# camera-ir-led.net
KiCad netlist of a schematic drawn in EAGLE
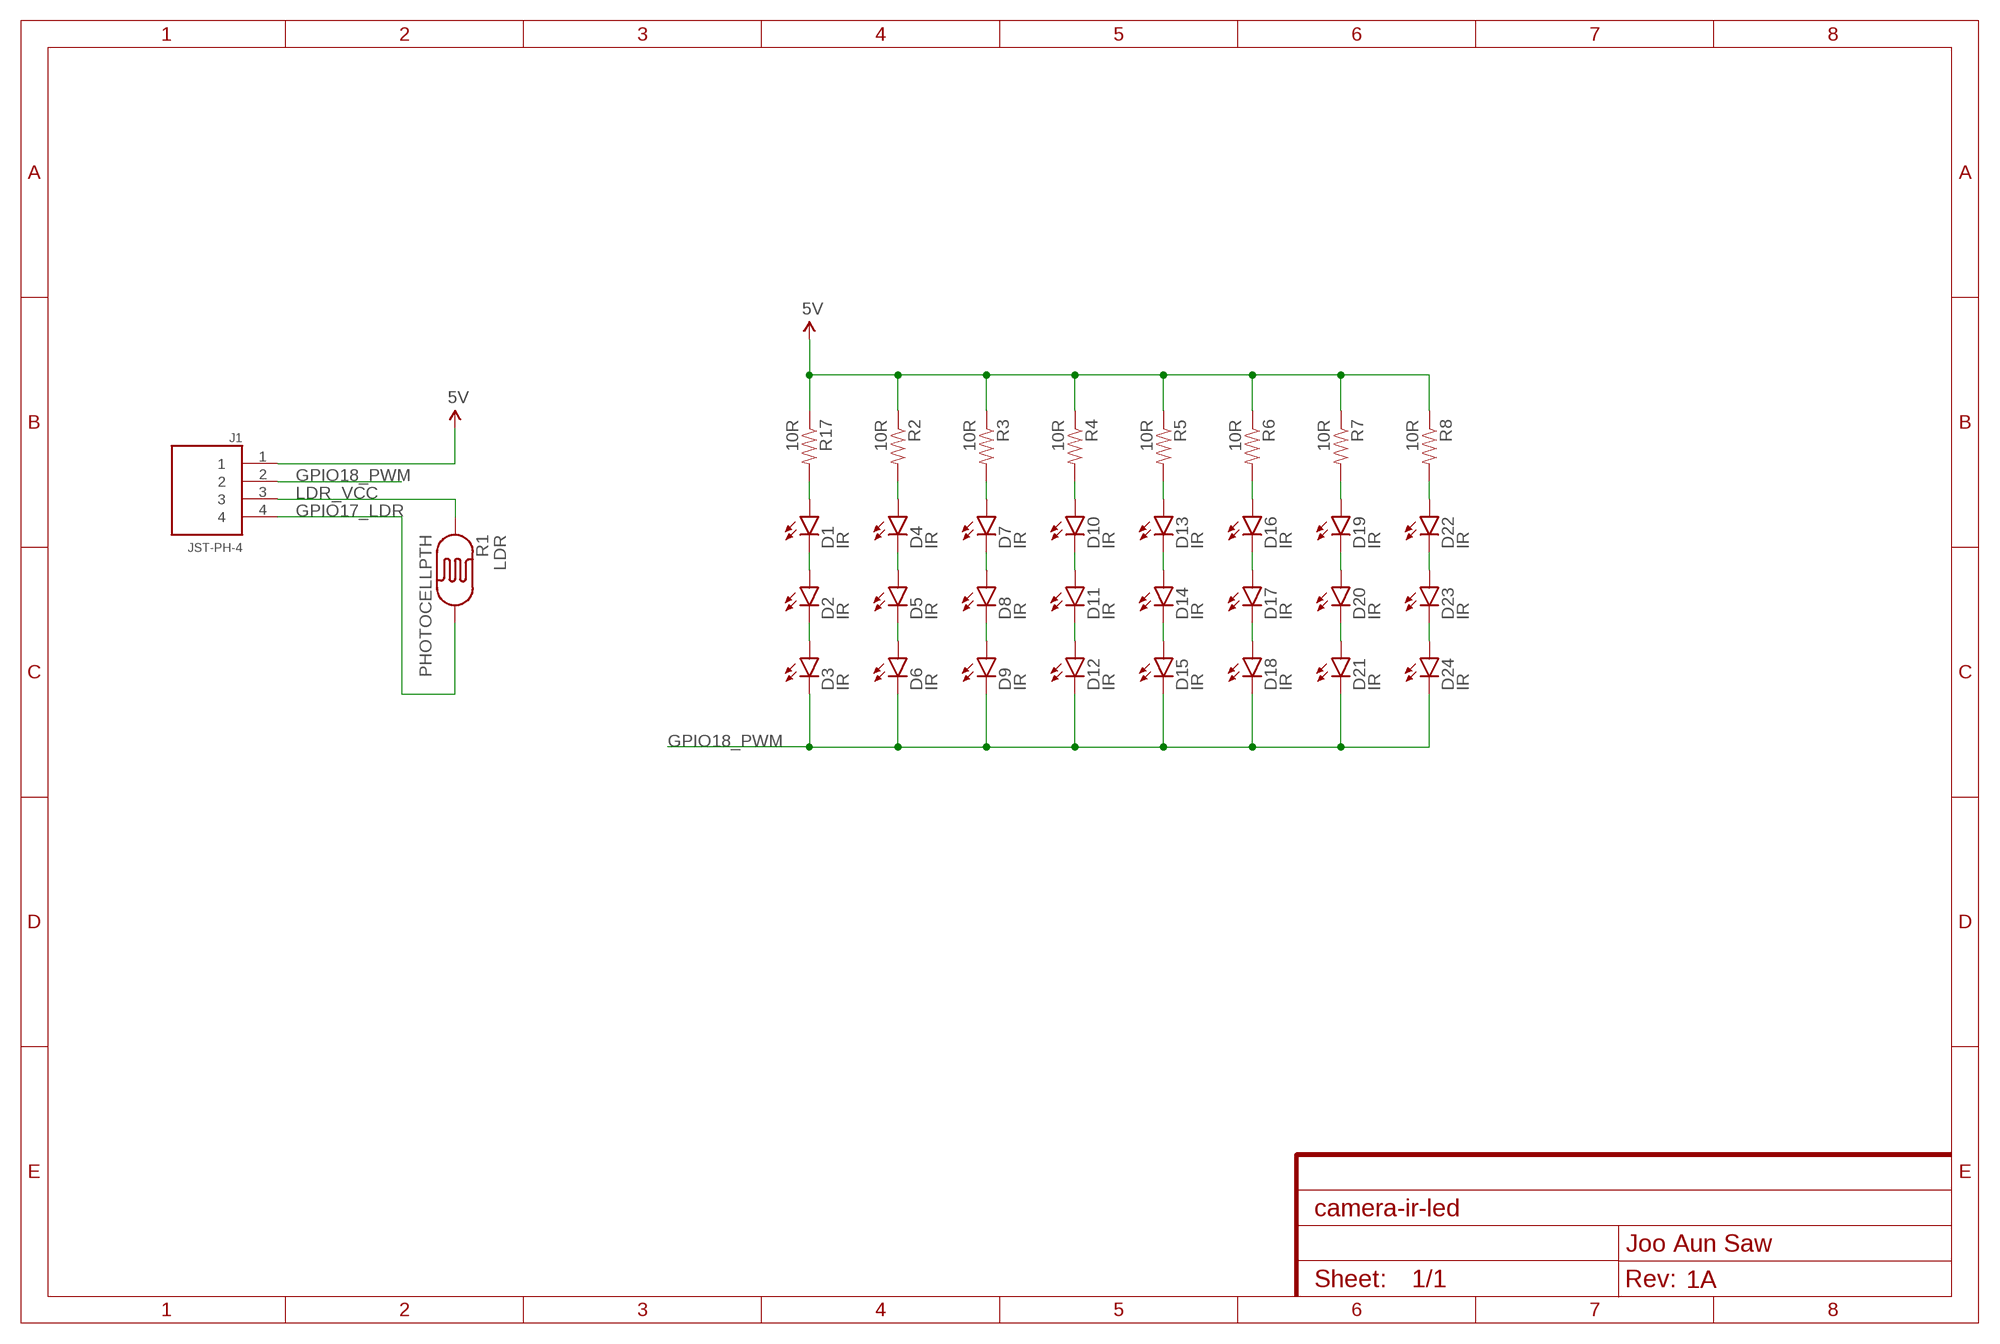
[diagram p0: schematic, sheet 1]

(export (version "E")
  (design (tool "Eeschema 10.0.6"))
  (components
    (comp (ref "D1")
      (value "IR")
      (footprint "eagle-import:LED5MM")
      (libsource (lib "eagle-import") (part "LED5MM"))
    )
    (comp (ref "D2")
      (value "IR")
      (footprint "eagle-import:LED5MM")
      (libsource (lib "eagle-import") (part "LED5MM"))
    )
    (comp (ref "D3")
      (value "IR")
      (footprint "eagle-import:LED5MM")
      (libsource (lib "eagle-import") (part "LED5MM"))
    )
    (comp (ref "D4")
      (value "IR")
      (footprint "eagle-import:LED5MM")
      (libsource (lib "eagle-import") (part "LED5MM"))
    )
    (comp (ref "D5")
      (value "IR")
      (footprint "eagle-import:LED5MM")
      (libsource (lib "eagle-import") (part "LED5MM"))
    )
    (comp (ref "D6")
      (value "IR")
      (footprint "eagle-import:LED5MM")
      (libsource (lib "eagle-import") (part "LED5MM"))
    )
    (comp (ref "D7")
      (value "IR")
      (footprint "eagle-import:LED5MM")
      (libsource (lib "eagle-import") (part "LED5MM"))
    )
    (comp (ref "D8")
      (value "IR")
      (footprint "eagle-import:LED5MM")
      (libsource (lib "eagle-import") (part "LED5MM"))
    )
    (comp (ref "D9")
      (value "IR")
      (footprint "eagle-import:LED5MM")
      (libsource (lib "eagle-import") (part "LED5MM"))
    )
    (comp (ref "D10")
      (value "IR")
      (footprint "eagle-import:LED5MM")
      (libsource (lib "eagle-import") (part "LED5MM"))
    )
    (comp (ref "D11")
      (value "IR")
      (footprint "eagle-import:LED5MM")
      (libsource (lib "eagle-import") (part "LED5MM"))
    )
    (comp (ref "D12")
      (value "IR")
      (footprint "eagle-import:LED5MM")
      (libsource (lib "eagle-import") (part "LED5MM"))
    )
    (comp (ref "D13")
      (value "IR")
      (footprint "eagle-import:LED5MM")
      (libsource (lib "eagle-import") (part "LED5MM"))
    )
    (comp (ref "D14")
      (value "IR")
      (footprint "eagle-import:LED5MM")
      (libsource (lib "eagle-import") (part "LED5MM"))
    )
    (comp (ref "D15")
      (value "IR")
      (footprint "eagle-import:LED5MM")
      (libsource (lib "eagle-import") (part "LED5MM"))
    )
    (comp (ref "D16")
      (value "IR")
      (footprint "eagle-import:LED5MM")
      (libsource (lib "eagle-import") (part "LED5MM"))
    )
    (comp (ref "D17")
      (value "IR")
      (footprint "eagle-import:LED5MM")
      (libsource (lib "eagle-import") (part "LED5MM"))
    )
    (comp (ref "D18")
      (value "IR")
      (footprint "eagle-import:LED5MM")
      (libsource (lib "eagle-import") (part "LED5MM"))
    )
    (comp (ref "D19")
      (value "IR")
      (footprint "eagle-import:LED5MM")
      (libsource (lib "eagle-import") (part "LED5MM"))
    )
    (comp (ref "D20")
      (value "IR")
      (footprint "eagle-import:LED5MM")
      (libsource (lib "eagle-import") (part "LED5MM"))
    )
    (comp (ref "D21")
      (value "IR")
      (footprint "eagle-import:LED5MM")
      (libsource (lib "eagle-import") (part "LED5MM"))
    )
    (comp (ref "D22")
      (value "IR")
      (footprint "eagle-import:LED5MM")
      (libsource (lib "eagle-import") (part "LED5MM"))
    )
    (comp (ref "D23")
      (value "IR")
      (footprint "eagle-import:LED5MM")
      (libsource (lib "eagle-import") (part "LED5MM"))
    )
    (comp (ref "D24")
      (value "IR")
      (footprint "eagle-import:LED5MM")
      (libsource (lib "eagle-import") (part "LED5MM"))
    )
    (comp (ref "J1")
      (value "JST-PH-4")
      (footprint "eagle-import:JST-PH-4-POS-TH")
      (libsource (lib "eagle-import") (part "CONNECTOR-4-POS-THJST-PH-4"))
    )
    (comp (ref "R1")
      (value "PHOTOCELLPTH")
      (footprint "eagle-import:PHOTOCELL")
      (fields (field (name "PARTNO") "GL5528"))
      (libsource (lib "eagle-import") (part "PHOTOCELLPTH"))
    )
    (comp (ref "R2")
      (value "10R")
      (footprint "eagle-import:0805")
      (fields (field (name "PARTNO") "RC0805JR-0710RL"))
      (libsource (lib "eagle-import") (part "RESISTOR0805-RES"))
    )
    (comp (ref "R3")
      (value "10R")
      (footprint "eagle-import:0805")
      (fields (field (name "PARTNO") "RC0805JR-0710RL"))
      (libsource (lib "eagle-import") (part "RESISTOR0805-RES"))
    )
    (comp (ref "R4")
      (value "10R")
      (footprint "eagle-import:0805")
      (fields (field (name "PARTNO") "RC0805JR-0710RL"))
      (libsource (lib "eagle-import") (part "RESISTOR0805-RES"))
    )
    (comp (ref "R5")
      (value "10R")
      (footprint "eagle-import:0805")
      (fields (field (name "PARTNO") "RC0805JR-0710RL"))
      (libsource (lib "eagle-import") (part "RESISTOR0805-RES"))
    )
    (comp (ref "R6")
      (value "10R")
      (footprint "eagle-import:0805")
      (fields (field (name "PARTNO") "RC0805JR-0710RL"))
      (libsource (lib "eagle-import") (part "RESISTOR0805-RES"))
    )
    (comp (ref "R7")
      (value "10R")
      (footprint "eagle-import:0805")
      (fields (field (name "PARTNO") "RC0805JR-0710RL"))
      (libsource (lib "eagle-import") (part "RESISTOR0805-RES"))
    )
    (comp (ref "R8")
      (value "10R")
      (footprint "eagle-import:0805")
      (fields (field (name "PARTNO") "RC0805JR-0710RL"))
      (libsource (lib "eagle-import") (part "RESISTOR0805-RES"))
    )
    (comp (ref "R17")
      (value "10R")
      (footprint "eagle-import:0805")
      (fields (field (name "PARTNO") "RC0805JR-0710RL"))
      (libsource (lib "eagle-import") (part "RESISTOR0805-RES"))
    )
  )
  (nets
    (net (code "1") (name "/GPIO17_LDR") (class "Default")
      (node (ref "J1") (pin "4") (pinfunction "4_4") (pintype "bidirectional"))
      (node (ref "R1") (pin "2") (pinfunction "P$2_2") (pintype "bidirectional"))
    )
    (net (code "2") (name "/GPIO18_PWM") (class "Default")
      (node (ref "D12") (pin "K") (pinfunction "C_K") (pintype "passive"))
      (node (ref "D15") (pin "K") (pinfunction "C_K") (pintype "passive"))
      (node (ref "D18") (pin "K") (pinfunction "C_K") (pintype "passive"))
      (node (ref "D21") (pin "K") (pinfunction "C_K") (pintype "passive"))
      (node (ref "D24") (pin "K") (pinfunction "C_K") (pintype "passive"))
      (node (ref "D3") (pin "K") (pinfunction "C_K") (pintype "passive"))
      (node (ref "D6") (pin "K") (pinfunction "C_K") (pintype "passive"))
      (node (ref "D9") (pin "K") (pinfunction "C_K") (pintype "passive"))
      (node (ref "J1") (pin "2") (pinfunction "2_2") (pintype "bidirectional"))
    )
    (net (code "3") (name "/LDR_VCC") (class "Default")
      (node (ref "J1") (pin "3") (pinfunction "3_3") (pintype "bidirectional"))
      (node (ref "R1") (pin "1") (pinfunction "P$1_1") (pintype "bidirectional"))
    )
    (net (code "4") (name "5V") (class "Default")
      (node (ref "J1") (pin "1") (pinfunction "1_1") (pintype "bidirectional"))
      (node (ref "R17") (pin "1") (pinfunction "1_1") (pintype "passive"))
      (node (ref "R2") (pin "1") (pinfunction "1_1") (pintype "passive"))
      (node (ref "R3") (pin "1") (pinfunction "1_1") (pintype "passive"))
      (node (ref "R4") (pin "1") (pinfunction "1_1") (pintype "passive"))
      (node (ref "R5") (pin "1") (pinfunction "1_1") (pintype "passive"))
      (node (ref "R6") (pin "1") (pinfunction "1_1") (pintype "passive"))
      (node (ref "R7") (pin "1") (pinfunction "1_1") (pintype "passive"))
      (node (ref "R8") (pin "1") (pinfunction "1_1") (pintype "passive"))
    )
    (net (code "5") (name "Net-(D1-C)") (class "Default")
      (node (ref "D1") (pin "K") (pinfunction "C_K") (pintype "passive"))
      (node (ref "D2") (pin "A") (pinfunction "A_A") (pintype "passive"))
    )
    (net (code "6") (name "Net-(D1-PadA)") (class "Default")
      (node (ref "D1") (pin "A") (pinfunction "A_A") (pintype "passive"))
      (node (ref "R17") (pin "2") (pinfunction "2_2") (pintype "passive"))
    )
    (net (code "7") (name "Net-(D2-C)") (class "Default")
      (node (ref "D2") (pin "K") (pinfunction "C_K") (pintype "passive"))
      (node (ref "D3") (pin "A") (pinfunction "A_A") (pintype "passive"))
    )
    (net (code "8") (name "Net-(D4-C)") (class "Default")
      (node (ref "D4") (pin "K") (pinfunction "C_K") (pintype "passive"))
      (node (ref "D5") (pin "A") (pinfunction "A_A") (pintype "passive"))
    )
    (net (code "9") (name "Net-(D4-PadA)") (class "Default")
      (node (ref "D4") (pin "A") (pinfunction "A_A") (pintype "passive"))
      (node (ref "R2") (pin "2") (pinfunction "2_2") (pintype "passive"))
    )
    (net (code "10") (name "Net-(D5-C)") (class "Default")
      (node (ref "D5") (pin "K") (pinfunction "C_K") (pintype "passive"))
      (node (ref "D6") (pin "A") (pinfunction "A_A") (pintype "passive"))
    )
    (net (code "11") (name "Net-(D7-C)") (class "Default")
      (node (ref "D7") (pin "K") (pinfunction "C_K") (pintype "passive"))
      (node (ref "D8") (pin "A") (pinfunction "A_A") (pintype "passive"))
    )
    (net (code "12") (name "Net-(D7-PadA)") (class "Default")
      (node (ref "D7") (pin "A") (pinfunction "A_A") (pintype "passive"))
      (node (ref "R3") (pin "2") (pinfunction "2_2") (pintype "passive"))
    )
    (net (code "13") (name "Net-(D8-C)") (class "Default")
      (node (ref "D8") (pin "K") (pinfunction "C_K") (pintype "passive"))
      (node (ref "D9") (pin "A") (pinfunction "A_A") (pintype "passive"))
    )
    (net (code "14") (name "Net-(D10-C)") (class "Default")
      (node (ref "D10") (pin "K") (pinfunction "C_K") (pintype "passive"))
      (node (ref "D11") (pin "A") (pinfunction "A_A") (pintype "passive"))
    )
    (net (code "15") (name "Net-(D10-PadA)") (class "Default")
      (node (ref "D10") (pin "A") (pinfunction "A_A") (pintype "passive"))
      (node (ref "R4") (pin "2") (pinfunction "2_2") (pintype "passive"))
    )
    (net (code "16") (name "Net-(D11-C)") (class "Default")
      (node (ref "D11") (pin "K") (pinfunction "C_K") (pintype "passive"))
      (node (ref "D12") (pin "A") (pinfunction "A_A") (pintype "passive"))
    )
    (net (code "17") (name "Net-(D13-C)") (class "Default")
      (node (ref "D13") (pin "K") (pinfunction "C_K") (pintype "passive"))
      (node (ref "D14") (pin "A") (pinfunction "A_A") (pintype "passive"))
    )
    (net (code "18") (name "Net-(D13-PadA)") (class "Default")
      (node (ref "D13") (pin "A") (pinfunction "A_A") (pintype "passive"))
      (node (ref "R5") (pin "2") (pinfunction "2_2") (pintype "passive"))
    )
    (net (code "19") (name "Net-(D14-C)") (class "Default")
      (node (ref "D14") (pin "K") (pinfunction "C_K") (pintype "passive"))
      (node (ref "D15") (pin "A") (pinfunction "A_A") (pintype "passive"))
    )
    (net (code "20") (name "Net-(D16-C)") (class "Default")
      (node (ref "D16") (pin "K") (pinfunction "C_K") (pintype "passive"))
      (node (ref "D17") (pin "A") (pinfunction "A_A") (pintype "passive"))
    )
    (net (code "21") (name "Net-(D16-PadA)") (class "Default")
      (node (ref "D16") (pin "A") (pinfunction "A_A") (pintype "passive"))
      (node (ref "R6") (pin "2") (pinfunction "2_2") (pintype "passive"))
    )
    (net (code "22") (name "Net-(D17-C)") (class "Default")
      (node (ref "D17") (pin "K") (pinfunction "C_K") (pintype "passive"))
      (node (ref "D18") (pin "A") (pinfunction "A_A") (pintype "passive"))
    )
    (net (code "23") (name "Net-(D19-C)") (class "Default")
      (node (ref "D19") (pin "K") (pinfunction "C_K") (pintype "passive"))
      (node (ref "D20") (pin "A") (pinfunction "A_A") (pintype "passive"))
    )
    (net (code "24") (name "Net-(D19-PadA)") (class "Default")
      (node (ref "D19") (pin "A") (pinfunction "A_A") (pintype "passive"))
      (node (ref "R7") (pin "2") (pinfunction "2_2") (pintype "passive"))
    )
    (net (code "25") (name "Net-(D20-C)") (class "Default")
      (node (ref "D20") (pin "K") (pinfunction "C_K") (pintype "passive"))
      (node (ref "D21") (pin "A") (pinfunction "A_A") (pintype "passive"))
    )
    (net (code "26") (name "Net-(D22-C)") (class "Default")
      (node (ref "D22") (pin "K") (pinfunction "C_K") (pintype "passive"))
      (node (ref "D23") (pin "A") (pinfunction "A_A") (pintype "passive"))
    )
    (net (code "27") (name "Net-(D22-PadA)") (class "Default")
      (node (ref "D22") (pin "A") (pinfunction "A_A") (pintype "passive"))
      (node (ref "R8") (pin "2") (pinfunction "2_2") (pintype "passive"))
    )
    (net (code "28") (name "Net-(D23-C)") (class "Default")
      (node (ref "D23") (pin "K") (pinfunction "C_K") (pintype "passive"))
      (node (ref "D24") (pin "A") (pinfunction "A_A") (pintype "passive"))
    )
  )
)
